# apd_v1_0.net
KiCad netlist of a schematic drawn in EAGLE
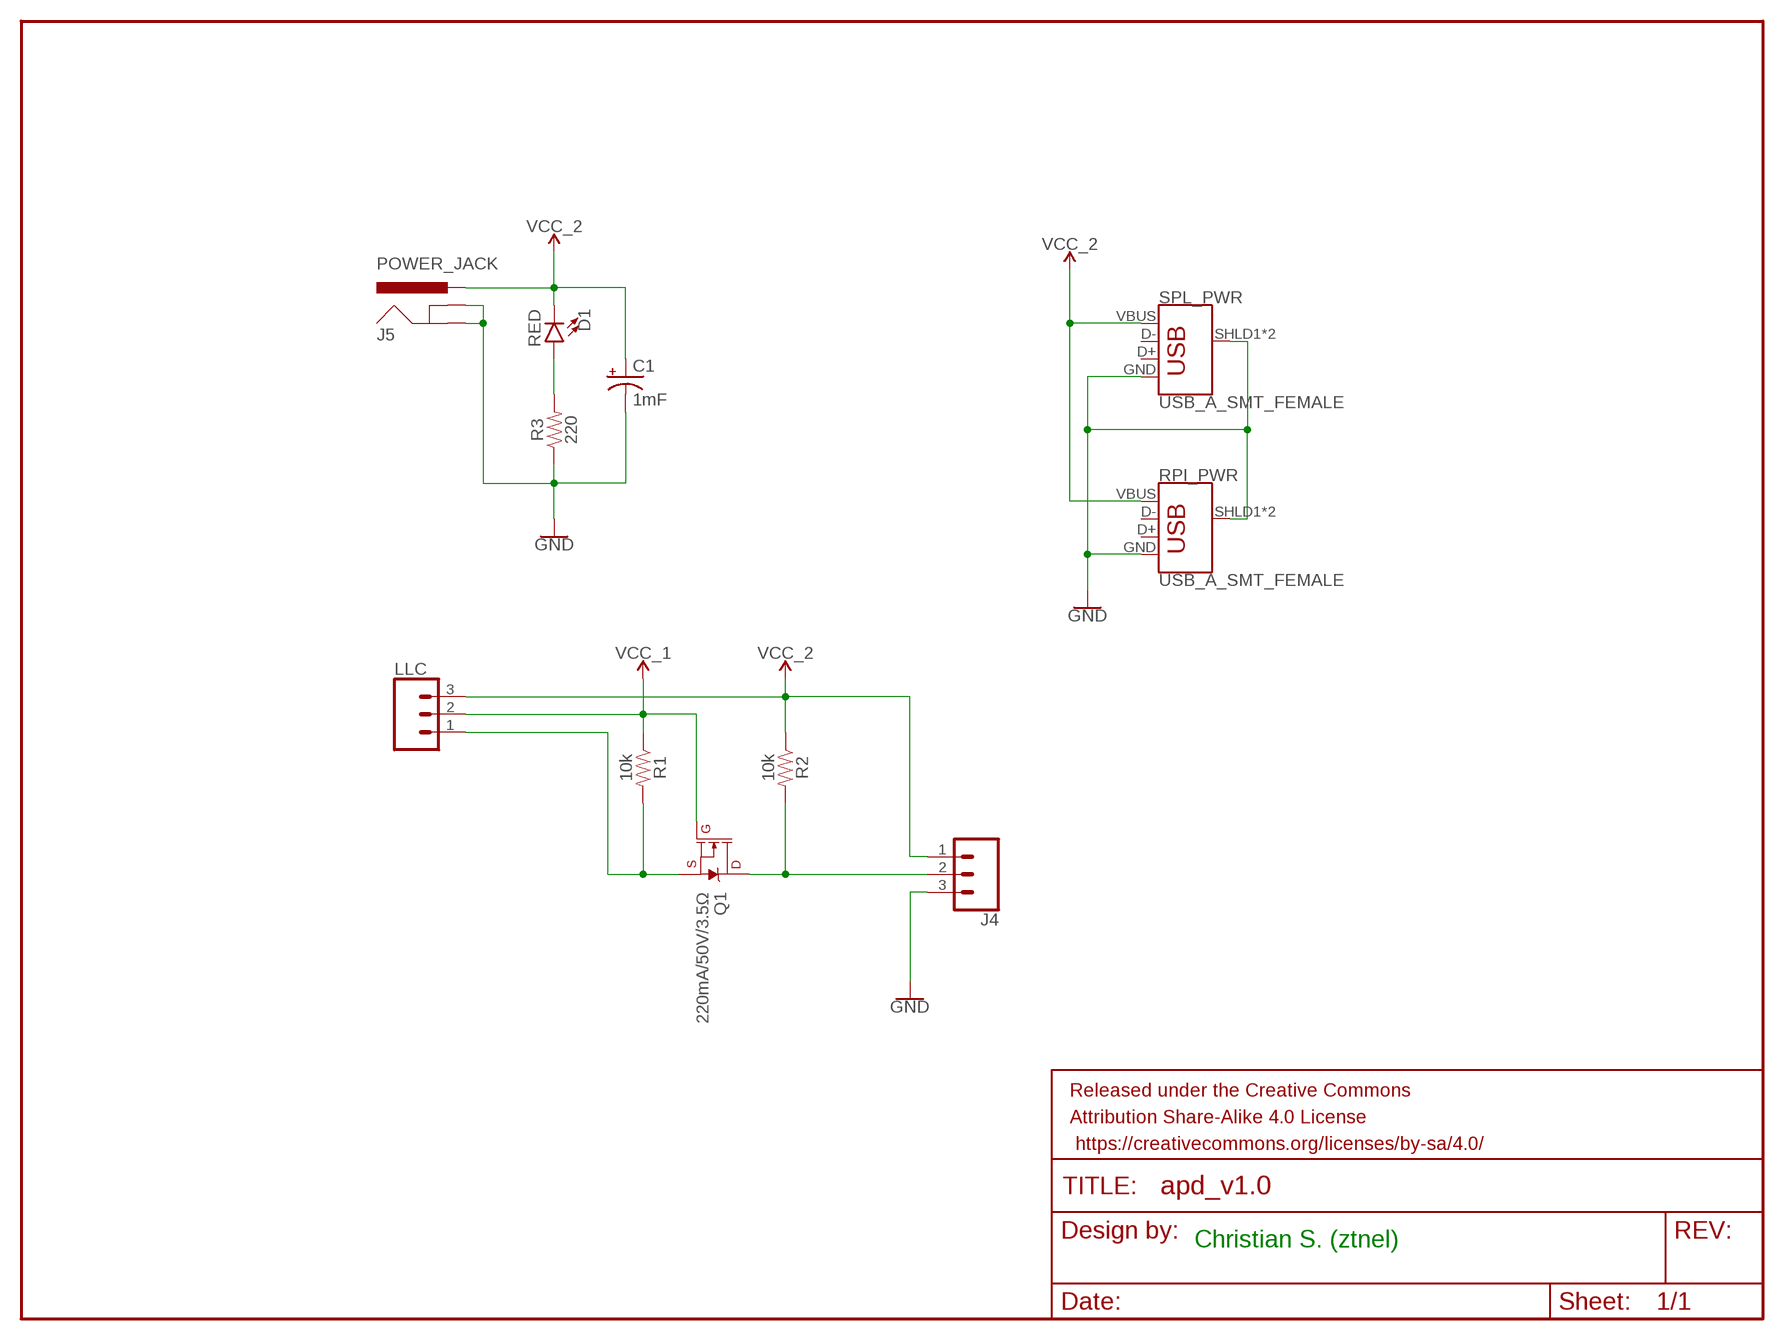
[diagram p0: schematic, sheet 1]

(export (version "E")
  (design (tool "Eeschema 10.0.6"))
  (components
    (comp (ref "C1")
      (value "1mF")
      (footprint "eagle-import:CPOL-RADIAL-5MM-10MM")
      (libsource (lib "eagle-import") (part "1000UF-RADIAL-5MM-25V-20%"))
    )
    (comp (ref "D1")
      (value "RED")
      (footprint "eagle-import:LED-0603")
      (libsource (lib "eagle-import") (part "LED-RED0603"))
    )
    (comp (ref "FRAME1")
      (value "FRAME-LETTER")
      (footprint "eagle-import:CREATIVE_COMMONS")
      (libsource (lib "eagle-import") (part "FRAME-LETTER"))
    )
    (comp (ref "J4")
      (value "CONN_03JST-PTH-VERT")
      (footprint "eagle-import:JST-3-PTH-VERT")
      (libsource (lib "eagle-import") (part "CONN_03JST-PTH-VERT"))
    )
    (comp (ref "J5")
      (value "POWER_JACK")
      (footprint "eagle-import:POWER_JACK_PTH")
      (libsource (lib "eagle-import") (part "POWER_JACK"))
    )
    (comp (ref "LLC")
      (value "CONN_03")
      (footprint "eagle-import:1X03")
      (libsource (lib "eagle-import") (part "CONN_03"))
    )
    (comp (ref "Q1")
      (value "220mA/50V/3.5Ω")
      (footprint "eagle-import:SOT23-3")
      (libsource (lib "eagle-import") (part "MOSFET-NCH-BSS138"))
    )
    (comp (ref "R1")
      (value "10k")
      (footprint "eagle-import:0603")
      (libsource (lib "eagle-import") (part "10KOHM-0603-1/10W-1%"))
    )
    (comp (ref "R2")
      (value "10k")
      (footprint "eagle-import:0603")
      (libsource (lib "eagle-import") (part "10KOHM-0603-1/10W-1%"))
    )
    (comp (ref "R3")
      (value "220")
      (footprint "eagle-import:0603")
      (libsource (lib "eagle-import") (part "220OHM-0603-1/10W-1%"))
    )
    (comp (ref "RPI_PWR")
      (value "USB_A_SMT_FEMALE")
      (footprint "eagle-import:USB-A-S-SILK-FEMALE")
      (libsource (lib "eagle-import") (part "USB_A_SMT_FEMALE"))
    )
    (comp (ref "SPL_PWR")
      (value "USB_A_SMT_FEMALE")
      (footprint "eagle-import:USB-A-S-SILK-FEMALE")
      (libsource (lib "eagle-import") (part "USB_A_SMT_FEMALE"))
    )
  )
  (nets
    (net (code "1") (name "GND") (class "Default")
      (node (ref "C1") (pin "-") (pinfunction "-_-") (pintype "passive"))
      (node (ref "J4") (pin "3") (pinfunction "3_3") (pintype "passive"))
      (node (ref "J5") (pin "GND") (pinfunction "GND_GND") (pintype "bidirectional"))
      (node (ref "J5") (pin "GNDBREAK") (pinfunction "GNDBREAK_GNDBREAK") (pintype "bidirectional"))
      (node (ref "R3") (pin "1") (pinfunction "1_1") (pintype "passive"))
      (node (ref "RPI_PWR") (pin "GND") (pinfunction "GND_GND") (pintype "power_in"))
      (node (ref "RPI_PWR") (pin "SHLD1") (pinfunction "SHIELD_SHLD1") (pintype "bidirectional"))
      (node (ref "RPI_PWR") (pin "SHLD2") (pinfunction "SHIELD_SHLD2") (pintype "bidirectional"))
      (node (ref "SPL_PWR") (pin "GND") (pinfunction "GND_GND") (pintype "power_in"))
      (node (ref "SPL_PWR") (pin "SHLD1") (pinfunction "SHIELD_SHLD1") (pintype "bidirectional"))
      (node (ref "SPL_PWR") (pin "SHLD2") (pinfunction "SHIELD_SHLD2") (pintype "bidirectional"))
    )
    (net (code "2") (name "Net-(D1-PadA)") (class "Default")
      (node (ref "D1") (pin "A") (pinfunction "A_A") (pintype "passive"))
      (node (ref "R3") (pin "2") (pinfunction "2_2") (pintype "passive"))
    )
    (net (code "3") (name "Net-(Q1-D)") (class "Default")
      (node (ref "J4") (pin "2") (pinfunction "2_2") (pintype "passive"))
      (node (ref "Q1") (pin "3") (pinfunction "D_3") (pintype "bidirectional"))
      (node (ref "R2") (pin "2") (pinfunction "2_2") (pintype "passive"))
    )
    (net (code "4") (name "Net-(Q1-S)") (class "Default")
      (node (ref "LLC") (pin "1") (pinfunction "1_1") (pintype "passive"))
      (node (ref "Q1") (pin "2") (pinfunction "S_2") (pintype "bidirectional"))
      (node (ref "R1") (pin "2") (pinfunction "2_2") (pintype "passive"))
    )
    (net (code "5") (name "VCC_1") (class "Default")
      (node (ref "LLC") (pin "2") (pinfunction "2_2") (pintype "passive"))
      (node (ref "Q1") (pin "1") (pinfunction "G_1") (pintype "bidirectional"))
      (node (ref "R1") (pin "1") (pinfunction "1_1") (pintype "passive"))
    )
    (net (code "6") (name "VCC_2") (class "Default")
      (node (ref "C1") (pin "+") (pinfunction "+_+") (pintype "passive"))
      (node (ref "D1") (pin "C") (pinfunction "C_C") (pintype "passive"))
      (node (ref "J4") (pin "1") (pinfunction "1_1") (pintype "passive"))
      (node (ref "J5") (pin "PWR") (pinfunction "PWR_PWR") (pintype "bidirectional"))
      (node (ref "LLC") (pin "3") (pinfunction "3_3") (pintype "passive"))
      (node (ref "R2") (pin "1") (pinfunction "1_1") (pintype "passive"))
      (node (ref "RPI_PWR") (pin "VBUS") (pinfunction "VBUS_VBUS") (pintype "power_in"))
      (node (ref "SPL_PWR") (pin "VBUS") (pinfunction "VBUS_VBUS") (pintype "power_in"))
    )
    (net (code "7") (name "unconnected-(RPI_PWR-PadD+)") (class "Default")
      (node (ref "RPI_PWR") (pin "D+") (pinfunction "D+_D+") (pintype "bidirectional"))
    )
    (net (code "8") (name "unconnected-(RPI_PWR-PadD-)") (class "Default")
      (node (ref "RPI_PWR") (pin "D-") (pinfunction "D-_D-") (pintype "bidirectional"))
    )
    (net (code "9") (name "unconnected-(SPL_PWR-PadD+)") (class "Default")
      (node (ref "SPL_PWR") (pin "D+") (pinfunction "D+_D+") (pintype "bidirectional"))
    )
    (net (code "10") (name "unconnected-(SPL_PWR-PadD-)") (class "Default")
      (node (ref "SPL_PWR") (pin "D-") (pinfunction "D-_D-") (pintype "bidirectional"))
    )
  )
)
